# Power_Distribution.net
KiCad netlist of a schematic drawn in Altium Designer
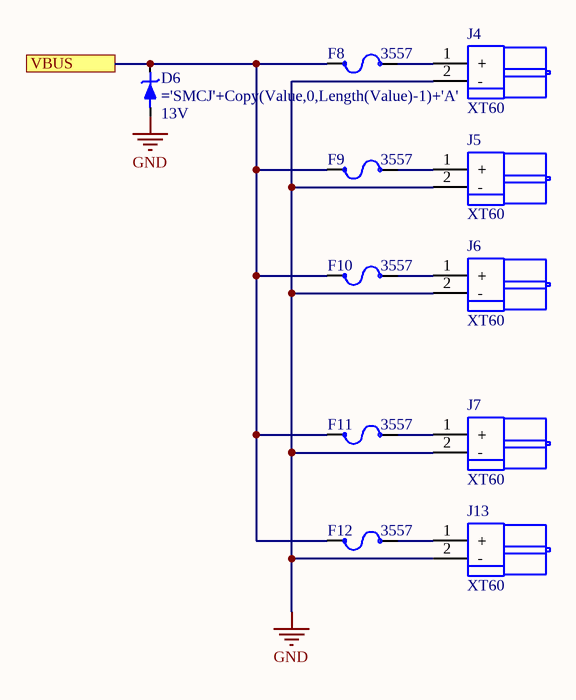
[diagram p0: Power_Distribution.SchDoc]

(export (version "E")
  (design (tool "Eeschema 10.0.6"))
  (components
    (comp (ref "D6")
      (value "13V")
      (footprint "SMC")
      (description "SMC Unidirectional TVS Diode")
      (fields
        (field (name "MANUFACTURER") "Vishay")
        (field (name "MANUFACTURER PN") "SMCJA")
        (field (name "Comment") "TVS Diode")
      )
      (libsource (lib "diode") (part "D_TVS_SMCJ_Uni_generic"))
    )
    (comp (ref "F8")
      (value "3557")
      (footprint "F_3557_Mini")
      (fields (field (name "MANUFACTURER") "Keystone Electronics") (field (name "VOLTAGE") "500V"))
      (libsource (lib "misc") (part "F_3557_MINI_ATO"))
    )
    (comp (ref "F9")
      (value "3557")
      (footprint "F_3557_Mini")
      (fields (field (name "MANUFACTURER") "Keystone Electronics") (field (name "VOLTAGE") "500V"))
      (libsource (lib "misc") (part "F_3557_MINI_ATO"))
    )
    (comp (ref "F10")
      (value "3557")
      (footprint "F_3557_Mini")
      (fields (field (name "MANUFACTURER") "Keystone Electronics") (field (name "VOLTAGE") "500V"))
      (libsource (lib "misc") (part "F_3557_MINI_ATO"))
    )
    (comp (ref "F11")
      (value "3557")
      (footprint "F_3557_Mini")
      (fields (field (name "MANUFACTURER") "Keystone Electronics") (field (name "VOLTAGE") "500V"))
      (libsource (lib "misc") (part "F_3557_MINI_ATO"))
    )
    (comp (ref "F12")
      (value "3557")
      (footprint "F_3557_Mini")
      (fields (field (name "MANUFACTURER") "Keystone Electronics") (field (name "VOLTAGE") "500V"))
      (libsource (lib "misc") (part "F_3557_MINI_ATO"))
    )
    (comp (ref "J4")
      (value "XT60")
      (footprint "J_XT60_Thru_Female")
      (description "60 Amp XT60 Connector")
      (libsource (lib "connector") (part "J_XT60"))
    )
    (comp (ref "J5")
      (value "XT60")
      (footprint "J_XT60_Thru_Female")
      (description "60 Amp XT60 Connector")
      (libsource (lib "connector") (part "J_XT60"))
    )
    (comp (ref "J6")
      (value "XT60")
      (footprint "J_XT60_Thru_Female")
      (description "60 Amp XT60 Connector")
      (libsource (lib "connector") (part "J_XT60"))
    )
    (comp (ref "J7")
      (value "XT60")
      (footprint "J_XT60_SMD_Female")
      (description "60 Amp XT60 Connector")
      (libsource (lib "connector") (part "J_XT60"))
    )
    (comp (ref "J13")
      (value "XT60")
      (footprint "J_XT60_SMD_Female")
      (description "60 Amp XT60 Connector")
      (libsource (lib "connector") (part "J_XT60"))
    )
  )
  (nets
    (net (code "1") (name "/VBUS") (class "Default")
      (node (ref "D6") (pin "2") (pinfunction "Cathode_2") (pintype "passive"))
      (node (ref "F10") (pin "1") (pinfunction "1_1") (pintype "passive"))
      (node (ref "F11") (pin "1") (pinfunction "1_1") (pintype "passive"))
      (node (ref "F12") (pin "1") (pinfunction "1_1") (pintype "passive"))
      (node (ref "F8") (pin "1") (pinfunction "1_1") (pintype "passive"))
      (node (ref "F9") (pin "1") (pinfunction "1_1") (pintype "passive"))
    )
    (net (code "2") (name "GND") (class "Default")
      (node (ref "D6") (pin "1") (pinfunction "Anode_1") (pintype "passive"))
      (node (ref "J13") (pin "2") (pinfunction "-_2") (pintype "passive"))
      (node (ref "J4") (pin "2") (pinfunction "-_2") (pintype "passive"))
      (node (ref "J5") (pin "2") (pinfunction "-_2") (pintype "passive"))
      (node (ref "J6") (pin "2") (pinfunction "-_2") (pintype "passive"))
      (node (ref "J7") (pin "2") (pinfunction "-_2") (pintype "passive"))
    )
    (net (code "3") (name "Net-(J4-+)") (class "Default")
      (node (ref "F8") (pin "2") (pinfunction "2_2") (pintype "passive"))
      (node (ref "J4") (pin "1") (pinfunction "+_1") (pintype "passive"))
    )
    (net (code "4") (name "Net-(J5-+)") (class "Default")
      (node (ref "F9") (pin "2") (pinfunction "2_2") (pintype "passive"))
      (node (ref "J5") (pin "1") (pinfunction "+_1") (pintype "passive"))
    )
    (net (code "5") (name "Net-(J6-+)") (class "Default")
      (node (ref "F10") (pin "2") (pinfunction "2_2") (pintype "passive"))
      (node (ref "J6") (pin "1") (pinfunction "+_1") (pintype "passive"))
    )
    (net (code "6") (name "Net-(J7-+)") (class "Default")
      (node (ref "F11") (pin "2") (pinfunction "2_2") (pintype "passive"))
      (node (ref "J7") (pin "1") (pinfunction "+_1") (pintype "passive"))
    )
    (net (code "7") (name "Net-(J13-+)") (class "Default")
      (node (ref "F12") (pin "2") (pinfunction "2_2") (pintype "passive"))
      (node (ref "J13") (pin "1") (pinfunction "+_1") (pintype "passive"))
    )
  )
)
